# 4_rf_path.net
KiCad netlist of a schematic drawn in Altium Designer
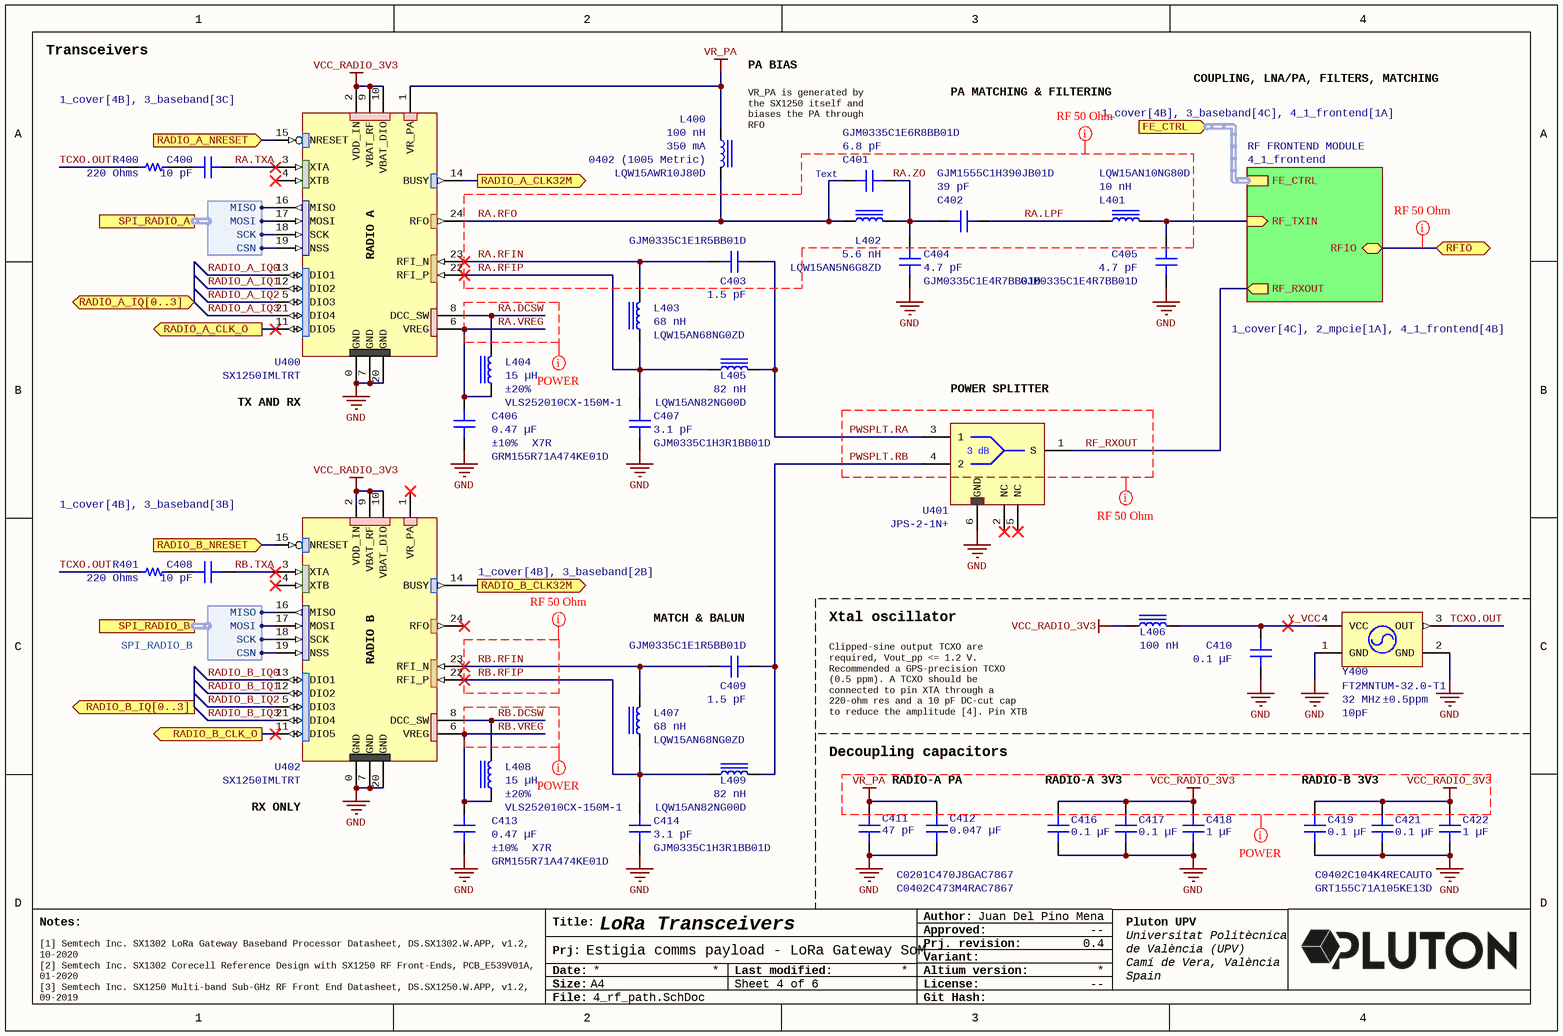
[diagram p0: 4_rf_path.SchDoc]

(export (version "E")
  (design (tool "Eeschema 10.0.6"))
  (components
    (comp (ref "C400")
      (value "10 pF")
      (footprint "CAP 0201_0603")
      (description "CAP CER 10PF 25V C0G/NP0 0201")
      (fields
        (field (name "PART NUMBER") "GJM0335C1E100GB01D")
        (field (name "MANUFACTURER") "Murata Electronics")
      )
      (libsource (lib "Celestial Altium Library - altium_library") (part "Capacitor"))
    )
    (comp (ref "C401")
      (value "6.8 pF")
      (footprint "CAP 0201_0603 RF")
      (description "CAP CER 6.8PF 25V C0G/NP0 0201")
      (fields
        (field (name "PART NUMBER") "GJM0335C1E6R8BB01D")
        (field (name "MANUFACTURER") "Murata Electronics")
        (field (name "TOLERANCE") "±0.1pF")
      )
      (libsource (lib "Celestial Altium Library - altium_library") (part "Capacitor"))
    )
    (comp (ref "C402")
      (value "39 pF")
      (footprint "CAP 0402_1005 RF")
      (description "CAP CER 39PF 50V C0G/NP0 0402")
      (fields
        (field (name "PART NUMBER") "GJM1555C1H390JB01D")
        (field (name "MANUFACTURER") "Murata Electronics")
        (field (name "TOLERANCE") "±5%")
      )
      (libsource (lib "Celestial Altium Library - altium_library") (part "Capacitor"))
    )
    (comp (ref "C403")
      (value "1.5 pF")
      (footprint "CAP 0201_0603 RF")
      (description "CAP CER 1.5PF 25V C0G/NP0 0201")
      (fields
        (field (name "PART NUMBER") "GJM0335C1E1R5BB01D")
        (field (name "CAPACITANCE") "1.5 pF")
        (field (name "MANUFACTURER") "Murata Electronics")
        (field (name "TOLERANCE") "±0.1pF")
      )
      (libsource (lib "Celestial Altium Library - altium_library") (part "Capacitor"))
    )
    (comp (ref "C404")
      (value "4.7 pF")
      (footprint "CAP 0201_0603 RF")
      (description "CAP CER 4.7PF 25V C0G/NP0 0201")
      (fields
        (field (name "PART NUMBER") "GJM0335C1E4R7BB01D")
        (field (name "MANUFACTURER") "Murata Electronics")
        (field (name "TOLERANCE") "±0.1pF")
      )
      (libsource (lib "Celestial Altium Library - altium_library") (part "Capacitor"))
    )
    (comp (ref "C405")
      (value "4.7 pF")
      (footprint "CAP 0201_0603 RF")
      (description "CAP CER 4.7PF 25V C0G/NP0 0201")
      (fields
        (field (name "PART NUMBER") "GJM0335C1E4R7BB01D")
        (field (name "MANUFACTURER") "Murata Electronics")
        (field (name "TOLERANCE") "±0.1pF")
      )
      (libsource (lib "Celestial Altium Library - altium_library") (part "Capacitor"))
    )
    (comp (ref "C406")
      (value "0.47 µF")
      (footprint "CAP 0402_1005")
      (description "CAP CER 0.47UF 10V X7R 0402")
      (fields
        (field (name "PART NUMBER") "GRM155R71A474KE01D")
        (field (name "MANUFACTURER") "Murata Electronics")
        (field (name "TEMPERATURE COEFFICIENT") "X7R")
        (field (name "TOLERANCE") "±10%")
      )
      (libsource (lib "Celestial Altium Library - altium_library") (part "Capacitor"))
    )
    (comp (ref "C407")
      (value "3.1 pF")
      (footprint "CAP 0201_0603 RF")
      (description "CAP CER 3.1PF 50V C0G/NP0 0201")
      (fields
        (field (name "PART NUMBER") "GJM0335C1H3R1BB01D")
        (field (name "CAPACITANCE") "3.1 pF")
        (field (name "MANUFACTURER") "Murata Electronics")
        (field (name "TOLERANCE") "±0.1pF")
      )
      (libsource (lib "Celestial Altium Library - altium_library") (part "Capacitor"))
    )
    (comp (ref "C408")
      (value "10 pF")
      (footprint "CAP 0201_0603")
      (description "CAP CER 10PF 25V C0G/NP0 0201")
      (fields
        (field (name "PART NUMBER") "GJM0335C1E100GB01D")
        (field (name "MANUFACTURER") "Murata Electronics")
      )
      (libsource (lib "Celestial Altium Library - altium_library") (part "Capacitor"))
    )
    (comp (ref "C409")
      (value "1.5 pF")
      (footprint "CAP 0201_0603 RF")
      (description "CAP CER 1.5PF 25V C0G/NP0 0201")
      (fields
        (field (name "PART NUMBER") "GJM0335C1E1R5BB01D")
        (field (name "CAPACITANCE") "1.5 pF")
        (field (name "MANUFACTURER") "Murata Electronics")
        (field (name "TOLERANCE") "±0.1pF")
      )
      (libsource (lib "Celestial Altium Library - altium_library") (part "Capacitor"))
    )
    (comp (ref "C410")
      (value "0.1 µF")
      (footprint "CAP 0402_1005")
      (description "CAP CER 0402 0.1UF 16V X7R 10%")
      (fields (field (name "PART NUMBER") "C0402C104K4RECAUTO") (field (name "MANUFACTURER") "KEMET"))
      (libsource (lib "Celestial Altium Library - altium_library") (part "Capacitor"))
    )
    (comp (ref "C411")
      (value "47 pF")
      (footprint "CAP 0201_0603")
      (description "CAP CER 47PF 10V C0G/NP0 0201")
      (fields
        (field (name "PART NUMBER") "C0201C470J8GAC7867")
        (field (name "MANUFACTURER") "KEMET")
        (field (name "TOLERANCE") "±5%")
      )
      (libsource (lib "Celestial Altium Library - altium_library") (part "Capacitor"))
    )
    (comp (ref "C412")
      (value "0.047 µF")
      (footprint "CAP 0402_1005")
      (description "CAP CER 0.047UF 16V X7R 0402")
      (fields
        (field (name "PART NUMBER") "C0402C473M4RAC7867")
        (field (name "MANUFACTURER") "KEMET")
        (field (name "TOLERANCE") "±20%")
      )
      (libsource (lib "Celestial Altium Library - altium_library") (part "Capacitor"))
    )
    (comp (ref "C413")
      (value "0.47 µF")
      (footprint "CAP 0402_1005")
      (description "CAP CER 0.47UF 10V X7R 0402")
      (fields
        (field (name "PART NUMBER") "GRM155R71A474KE01D")
        (field (name "MANUFACTURER") "Murata Electronics")
        (field (name "TEMPERATURE COEFFICIENT") "X7R")
        (field (name "TOLERANCE") "±10%")
      )
      (libsource (lib "Celestial Altium Library - altium_library") (part "Capacitor"))
    )
    (comp (ref "C414")
      (value "3.1 pF")
      (footprint "CAP 0201_0603 RF")
      (description "CAP CER 3.1PF 50V C0G/NP0 0201")
      (fields
        (field (name "PART NUMBER") "GJM0335C1H3R1BB01D")
        (field (name "CAPACITANCE") "3.1 pF")
        (field (name "MANUFACTURER") "Murata Electronics")
        (field (name "TOLERANCE") "±0.1pF")
      )
      (libsource (lib "Celestial Altium Library - altium_library") (part "Capacitor"))
    )
    (comp (ref "C416")
      (value "0.1 µF")
      (footprint "CAP 0402_1005")
      (description "CAP CER 0402 0.1UF 16V X7R 10%")
      (fields (field (name "PART NUMBER") "C0402C104K4RECAUTO") (field (name "MANUFACTURER") "KEMET"))
      (libsource (lib "Celestial Altium Library - altium_library") (part "Capacitor"))
    )
    (comp (ref "C417")
      (value "0.1 µF")
      (footprint "CAP 0402_1005")
      (description "CAP CER 0402 0.1UF 16V X7R 10%")
      (fields (field (name "PART NUMBER") "C0402C104K4RECAUTO") (field (name "MANUFACTURER") "KEMET"))
      (libsource (lib "Celestial Altium Library - altium_library") (part "Capacitor"))
    )
    (comp (ref "C418")
      (value "1 µF")
      (footprint "CAP 0402_1005")
      (description "CAP CER 1UF 10V X7S 0402")
      (fields
        (field (name "PART NUMBER") "GRT155C71A105KE13D")
        (field (name "MANUFACTURER") "Murata Electronics")
        (field (name "TOLERANCE") "±10%")
      )
      (libsource (lib "Celestial Altium Library - altium_library") (part "Capacitor"))
    )
    (comp (ref "C419")
      (value "0.1 µF")
      (footprint "CAP 0402_1005")
      (description "CAP CER 0402 0.1UF 16V X7R 10%")
      (fields
        (field (name "PART NUMBER") "C0402C104K4RECAUTO")
        (field (name "MANUFACTURER") "KEMET")
        (field (name "TOLERANCE") "±10%")
      )
      (libsource (lib "Celestial Altium Library - altium_library") (part "Capacitor"))
    )
    (comp (ref "C421")
      (value "0.1 µF")
      (footprint "CAP 0402_1005")
      (description "CAP CER 0402 0.1UF 16V X7R 10%")
      (fields (field (name "PART NUMBER") "C0402C104K4RECAUTO") (field (name "MANUFACTURER") "KEMET"))
      (libsource (lib "Celestial Altium Library - altium_library") (part "Capacitor"))
    )
    (comp (ref "C422")
      (value "1 µF")
      (footprint "CAP 0402_1005")
      (description "CAP CER 1UF 10V X7S 0402")
      (fields
        (field (name "PART NUMBER") "GRT155C71A105KE13D")
        (field (name "MANUFACTURER") "Murata Electronics")
      )
      (libsource (lib "Celestial Altium Library - altium_library") (part "Capacitor"))
    )
    (comp (ref "L400")
      (value "100 nH")
      (footprint "IND 0402_1005 RF WW")
      (description "FIXED IND 100NH 350MA 1OHM SMD")
      (fields
        (field (name "PART NUMBER") "LQW15AWR10J80D")
        (field (name "CURRENT RATING (AMPS)") "350 mA")
        (field (name "DEVICE PACKAGE") "0402 (1005 Metric)")
        (field (name "INDUCTANCE") "100 nH")
        (field (name "MANUFACTURER") "Murata Electronics")
        (field (name "TOLERANCE") "±5%")
      )
      (libsource (lib "Celestial Altium Library - altium_library") (part "Inductor"))
    )
    (comp (ref "L401")
      (value "10 nH")
      (footprint "IND 0402_1005 RF WW")
      (description "FIXED IND 10NH 1.4A 0.081OHM SMD")
      (fields
        (field (name "PART NUMBER") "LQW15AN10NG80D")
        (field (name "MANUFACTURER") "Murata Electronics")
        (field (name "TOLERANCE") "±2%")
      )
      (libsource (lib "Celestial Altium Library - altium_library") (part "Inductor"))
    )
    (comp (ref "L402")
      (value "5.6 nH")
      (footprint "IND 0402_1005 RF WW")
      (description "FIXED IND 5.6NH 1.77A 0.04OHM SM")
      (fields
        (field (name "PART NUMBER") "LQW15AN5N6G8ZD")
        (field (name "MANUFACTURER") "Murata Electronics")
        (field (name "TOLERANCE") "±2%")
      )
      (libsource (lib "Celestial Altium Library - altium_library") (part "Inductor"))
    )
    (comp (ref "L403")
      (value "68 nH")
      (footprint "IND 0402_1005 RF WW")
      (description "FIXED IND 68NH 140MA 1.96OHM SMD")
      (fields
        (field (name "PART NUMBER") "LQW15AN68NG0ZD")
        (field (name "INDUCTANCE") "68 nH")
        (field (name "MANUFACTURER") "Murata Electronics")
        (field (name "TOLERANCE") "±2%")
      )
      (libsource (lib "Celestial Altium Library - altium_library") (part "Inductor"))
    )
    (comp (ref "L404")
      (value "15 µH")
      (footprint "TDK VLS252010CX")
      (description "FIXED IND 15UH 560MA 914MOHM SMD")
      (fields
        (field (name "PART NUMBER") "VLS252010CX-150M-1")
        (field (name "INDUCTANCE") "15 µH")
        (field (name "MANUFACTURER") "TDK Corporation")
        (field (name "TOLERANCE") "±20%")
      )
      (libsource (lib "Celestial Altium Library - altium_library") (part "Inductor"))
    )
    (comp (ref "L405")
      (value "82 nH")
      (footprint "IND 0402_1005 RF WW")
      (description "FIXED IND 82NH 130MA 2.24OHM SMD")
      (fields
        (field (name "PART NUMBER") "LQW15AN82NG00D")
        (field (name "INDUCTANCE") "82 nH")
        (field (name "MANUFACTURER") "Murata Electronics")
        (field (name "TOLERANCE") "±2%")
      )
      (libsource (lib "Celestial Altium Library - altium_library") (part "Inductor"))
    )
    (comp (ref "L406")
      (value "100 nH")
      (footprint "IND 0402_1005 RF WW")
      (description "FIXED IND 100NH 350MA 1OHM SMD")
      (fields
        (field (name "PART NUMBER") "LQW15AWR10J80D")
        (field (name "INDUCTANCE") "100 nH")
        (field (name "MANUFACTURER") "Murata Electronics")
      )
      (libsource (lib "Celestial Altium Library - altium_library") (part "Inductor"))
    )
    (comp (ref "L407")
      (value "68 nH")
      (footprint "IND 0402_1005 RF WW")
      (description "FIXED IND 68NH 140MA 1.96OHM SMD")
      (fields
        (field (name "PART NUMBER") "LQW15AN68NG0ZD")
        (field (name "INDUCTANCE") "68 nH")
        (field (name "MANUFACTURER") "Murata Electronics")
        (field (name "TOLERANCE") "±2%")
      )
      (libsource (lib "Celestial Altium Library - altium_library") (part "Inductor"))
    )
    (comp (ref "L408")
      (value "15 µH")
      (footprint "TDK VLS252010CX")
      (description "FIXED IND 15UH 560MA 914MOHM SMD")
      (fields
        (field (name "PART NUMBER") "VLS252010CX-150M-1")
        (field (name "INDUCTANCE") "15 µH")
        (field (name "MANUFACTURER") "TDK Corporation")
        (field (name "TOLERANCE") "±20%")
      )
      (libsource (lib "Celestial Altium Library - altium_library") (part "Inductor"))
    )
    (comp (ref "L409")
      (value "82 nH")
      (footprint "IND 0402_1005 RF WW")
      (description "FIXED IND 82NH 130MA 2.24OHM SMD")
      (fields
        (field (name "PART NUMBER") "LQW15AN82NG00D")
        (field (name "INDUCTANCE") "82 nH")
        (field (name "MANUFACTURER") "Murata Electronics")
        (field (name "TOLERANCE") "±2%")
      )
      (libsource (lib "Celestial Altium Library - altium_library") (part "Inductor"))
    )
    (comp (ref "R400")
      (value "220 Ohms")
      (footprint "RES 0201_0603")
      (description "RES 220 OHM 1% 1/20W 0201")
      (fields (field (name "PART NUMBER") "RC0201FR-07220RL") (field (name "MANUFACTURER") "Yageo"))
      (libsource (lib "Celestial Altium Library - altium_library") (part "Resistor"))
    )
    (comp (ref "R401")
      (value "220 Ohms")
      (footprint "RES 0201_0603")
      (description "RES 220 OHM 1% 1/20W 0201")
      (fields (field (name "PART NUMBER") "RC0201FR-07220RL") (field (name "MANUFACTURER") "Yageo"))
      (libsource (lib "Celestial Altium Library - altium_library") (part "Resistor"))
    )
    (comp (ref "U400")
      (value "SX1250IMLTRT")
      (footprint "ics:QFN-24")
      (description "Sub-GHz RF Front End device. Supports up to +22 dBm output power on-chip")
      (libsource (lib "lora") (part "SX1250IMLTRT"))
    )
    (comp (ref "U401")
      (value "JPS-2-1N+")
      (footprint "SOP6-BH292-JPS-2-1N")
      (description "Power Splitter/Combiner, 2 Way, 0°, 50Ω, 350 to 550 MHz")
      (libsource (lib "rf") (part "JPS-2-1N+"))
    )
    (comp (ref "U402")
      (value "SX1250IMLTRT")
      (footprint "ics:QFN-24")
      (description "Sub-GHz RF Front End device. Supports up to +22 dBm output power on-chip")
      (libsource (lib "lora") (part "SX1250IMLTRT"))
    )
    (comp (ref "Y400")
      (value "FT2MNTUM-32.0-T1")
      (footprint "TCXO-XTAL-FT2MN")
      (fields
        (field (name "PART NUMBER") "FT2MNTUM-32.0-T1")
        (field (name "FREQUENCY") "32 MHz")
        (field (name "TOLERANCE") "±0.5ppm")
        (field (name "LOAD CAPACITANCE") "10pF")
      )
      (libsource (lib "rf") (part "FT2MNTUM-32.0-T1"))
    )
  )
  (nets
    (net (code "5") (name "/PWSPLT.RA") (class "Default")
      (node (ref "C403") (pin "2") (pinfunction "2_2") (pintype "passive"))
      (node (ref "L405") (pin "2") (pinfunction "2_2") (pintype "passive"))
      (node (ref "U401") (pin "3") (pinfunction "1_3") (pintype "passive"))
    )
    (net (code "6") (name "/PWSPLT.RB") (class "Default")
      (node (ref "C409") (pin "2") (pinfunction "2_2") (pintype "passive"))
      (node (ref "L409") (pin "2") (pinfunction "2_2") (pintype "passive"))
      (node (ref "U401") (pin "4") (pinfunction "2_4") (pintype "passive"))
    )
    (net (code "7") (name "/RA.DCSW") (class "Default")
      (node (ref "L404") (pin "2") (pinfunction "2_2") (pintype "passive"))
      (node (ref "U400") (pin "8") (pinfunction "DCC_SW_8") (pintype "power_in"))
    )
    (net (code "8") (name "/RA.LPF") (class "Default")
      (node (ref "C402") (pin "2") (pinfunction "2_2") (pintype "passive"))
      (node (ref "L401") (pin "1") (pinfunction "1_1") (pintype "passive"))
    )
    (net (code "9") (name "/RA.RFIN") (class "Default")
      (node (ref "C403") (pin "1") (pinfunction "1_1") (pintype "passive"))
      (node (ref "L403") (pin "2") (pinfunction "2_2") (pintype "passive"))
      (node (ref "U400") (pin "23") (pinfunction "RFI_N_23") (pintype "input"))
    )
    (net (code "10") (name "/RA.RFIP") (class "Default")
      (node (ref "C407") (pin "2") (pinfunction "2_2") (pintype "passive"))
      (node (ref "L403") (pin "1") (pinfunction "1_1") (pintype "passive"))
      (node (ref "L405") (pin "1") (pinfunction "1_1") (pintype "passive"))
      (node (ref "U400") (pin "22") (pinfunction "RFI_P_22") (pintype "input"))
    )
    (net (code "11") (name "/RA.RFO") (class "Default")
      (node (ref "C401") (pin "1") (pinfunction "1_1") (pintype "passive"))
      (node (ref "L400") (pin "2") (pinfunction "2_2") (pintype "passive"))
      (node (ref "L402") (pin "1") (pinfunction "1_1") (pintype "passive"))
      (node (ref "U400") (pin "24") (pinfunction "RFO_24") (pintype "output"))
    )
    (net (code "12") (name "/RA.TXA") (class "Default")
      (node (ref "C400") (pin "1") (pinfunction "1_1") (pintype "passive"))
      (node (ref "U400") (pin "3") (pinfunction "XTA_3") (pintype "input"))
    )
    (net (code "13") (name "/RA.VREG") (class "Default")
      (node (ref "C406") (pin "2") (pinfunction "2_2") (pintype "passive"))
      (node (ref "L404") (pin "1") (pinfunction "1_1") (pintype "passive"))
      (node (ref "U400") (pin "6") (pinfunction "VREG_6") (pintype "power_in"))
    )
    (net (code "14") (name "/RA.ZO") (class "Default")
      (node (ref "C401") (pin "2") (pinfunction "2_2") (pintype "passive"))
      (node (ref "C402") (pin "1") (pinfunction "1_1") (pintype "passive"))
      (node (ref "C404") (pin "2") (pinfunction "2_2") (pintype "passive"))
      (node (ref "L402") (pin "2") (pinfunction "2_2") (pintype "passive"))
    )
    (net (code "15") (name "/RADIO_A_CLK32M") (class "Default")
      (node (ref "U400") (pin "14") (pinfunction "BUSY_14") (pintype "output"))
    )
    (net (code "16") (name "/RADIO_A_CLK_O") (class "Default")
      (node (ref "U400") (pin "11") (pinfunction "DIO5_11") (pintype "bidirectional+no_connect"))
    )
    (net (code "17") (name "/RADIO_A_IQ0") (class "Default")
      (node (ref "U400") (pin "13") (pinfunction "DIO1_13") (pintype "bidirectional"))
    )
    (net (code "18") (name "/RADIO_A_IQ1") (class "Default")
      (node (ref "U400") (pin "12") (pinfunction "DIO2_12") (pintype "bidirectional"))
    )
    (net (code "19") (name "/RADIO_A_IQ2") (class "Default")
      (node (ref "U400") (pin "5") (pinfunction "DIO3_5") (pintype "bidirectional"))
    )
    (net (code "20") (name "/RADIO_A_IQ3") (class "Default")
      (node (ref "U400") (pin "21") (pinfunction "DIO4_21") (pintype "bidirectional"))
    )
    (net (code "22") (name "/RADIO_A_NRESET") (class "Default")
      (node (ref "U400") (pin "15") (pinfunction "NRESET_15") (pintype "input"))
    )
    (net (code "23") (name "/RADIO_B_CLK32M") (class "Default")
      (node (ref "U402") (pin "14") (pinfunction "BUSY_14") (pintype "output"))
    )
    (net (code "24") (name "/RADIO_B_CLK_O") (class "Default")
      (node (ref "U402") (pin "11") (pinfunction "DIO5_11") (pintype "bidirectional+no_connect"))
    )
    (net (code "25") (name "/RADIO_B_IQ0") (class "Default")
      (node (ref "U402") (pin "13") (pinfunction "DIO1_13") (pintype "bidirectional"))
    )
    (net (code "26") (name "/RADIO_B_IQ1") (class "Default")
      (node (ref "U402") (pin "12") (pinfunction "DIO2_12") (pintype "bidirectional"))
    )
    (net (code "27") (name "/RADIO_B_IQ2") (class "Default")
      (node (ref "U402") (pin "5") (pinfunction "DIO3_5") (pintype "bidirectional"))
    )
    (net (code "28") (name "/RADIO_B_IQ3") (class "Default")
      (node (ref "U402") (pin "21") (pinfunction "DIO4_21") (pintype "bidirectional"))
    )
    (net (code "30") (name "/RADIO_B_NRESET") (class "Default")
      (node (ref "U402") (pin "15") (pinfunction "NRESET_15") (pintype "input"))
    )
    (net (code "31") (name "/RB.DCSW") (class "Default")
      (node (ref "L408") (pin "2") (pinfunction "2_2") (pintype "passive"))
      (node (ref "U402") (pin "8") (pinfunction "DCC_SW_8") (pintype "power_in"))
    )
    (net (code "32") (name "/RB.RFIN") (class "Default")
      (node (ref "C409") (pin "1") (pinfunction "1_1") (pintype "passive"))
      (node (ref "L407") (pin "2") (pinfunction "2_2") (pintype "passive"))
      (node (ref "U402") (pin "23") (pinfunction "RFI_N_23") (pintype "input"))
    )
    (net (code "33") (name "/RB.RFIP") (class "Default")
      (node (ref "C414") (pin "2") (pinfunction "2_2") (pintype "passive"))
      (node (ref "L407") (pin "1") (pinfunction "1_1") (pintype "passive"))
      (node (ref "L409") (pin "1") (pinfunction "1_1") (pintype "passive"))
      (node (ref "U402") (pin "22") (pinfunction "RFI_P_22") (pintype "input"))
    )
    (net (code "34") (name "/RB.TXA") (class "Default")
      (node (ref "C408") (pin "1") (pinfunction "1_1") (pintype "passive"))
      (node (ref "U402") (pin "3") (pinfunction "XTA_3") (pintype "input"))
    )
    (net (code "35") (name "/RB.VREG") (class "Default")
      (node (ref "C413") (pin "2") (pinfunction "2_2") (pintype "passive"))
      (node (ref "L408") (pin "1") (pinfunction "1_1") (pintype "passive"))
      (node (ref "U402") (pin "6") (pinfunction "VREG_6") (pintype "power_in"))
    )
    (net (code "37") (name "/RF_RXOUT") (class "Default")
      (node (ref "U401") (pin "1") (pinfunction "S_1") (pintype "passive"))
    )
    (net (code "38") (name "/RF_TXIN") (class "Default")
      (node (ref "C405") (pin "2") (pinfunction "2_2") (pintype "passive"))
      (node (ref "L401") (pin "2") (pinfunction "2_2") (pintype "passive"))
    )
    (net (code "39") (name "/TCXO.OUT") (class "Default")
      (node (ref "R400") (pin "1") (pinfunction "1_1") (pintype "passive"))
      (node (ref "R401") (pin "1") (pinfunction "1_1") (pintype "passive"))
      (node (ref "Y400") (pin "3") (pinfunction "OUT_3") (pintype "output"))
    )
    (net (code "43") (name "/Y_VCC") (class "Default")
      (node (ref "C410") (pin "2") (pinfunction "2_2") (pintype "passive"))
      (node (ref "L406") (pin "2") (pinfunction "2_2") (pintype "passive"))
      (node (ref "Y400") (pin "4") (pinfunction "VCC_4") (pintype "power_in"))
    )
    (net (code "44") (name "GND") (class "Default")
      (node (ref "C404") (pin "1") (pinfunction "1_1") (pintype "passive"))
      (node (ref "C405") (pin "1") (pinfunction "1_1") (pintype "passive"))
      (node (ref "C406") (pin "1") (pinfunction "1_1") (pintype "passive"))
      (node (ref "C407") (pin "1") (pinfunction "1_1") (pintype "passive"))
      (node (ref "C410") (pin "1") (pinfunction "1_1") (pintype "passive"))
      (node (ref "C411") (pin "1") (pinfunction "1_1") (pintype "passive"))
      (node (ref "C412") (pin "1") (pinfunction "1_1") (pintype "passive"))
      (node (ref "C413") (pin "1") (pinfunction "1_1") (pintype "passive"))
      (node (ref "C414") (pin "1") (pinfunction "1_1") (pintype "passive"))
      (node (ref "C416") (pin "1") (pinfunction "1_1") (pintype "passive"))
      (node (ref "C417") (pin "1") (pinfunction "1_1") (pintype "passive"))
      (node (ref "C418") (pin "1") (pinfunction "1_1") (pintype "passive"))
      (node (ref "C419") (pin "1") (pinfunction "1_1") (pintype "passive"))
      (node (ref "C421") (pin "1") (pinfunction "1_1") (pintype "passive"))
      (node (ref "C422") (pin "1") (pinfunction "1_1") (pintype "passive"))
      (node (ref "U400") (pin "0") (pinfunction "GND_0") (pintype "power_in"))
      (node (ref "U400") (pin "20") (pinfunction "GND_20") (pintype "power_in"))
      (node (ref "U400") (pin "7") (pinfunction "GND_7") (pintype "power_in"))
      (node (ref "U401") (pin "6") (pinfunction "GND_6") (pintype "power_in"))
      (node (ref "U402") (pin "0") (pinfunction "GND_0") (pintype "power_in"))
      (node (ref "U402") (pin "20") (pinfunction "GND_20") (pintype "power_in"))
      (node (ref "U402") (pin "7") (pinfunction "GND_7") (pintype "power_in"))
      (node (ref "Y400") (pin "1") (pinfunction "GND_1") (pintype "power_in"))
      (node (ref "Y400") (pin "2") (pinfunction "GND_2") (pintype "power_in"))
    )
    (net (code "45") (name "Net-(C400-Pad2)") (class "Default")
      (node (ref "C400") (pin "2") (pinfunction "2_2") (pintype "passive"))
      (node (ref "R400") (pin "2") (pinfunction "2_2") (pintype "passive"))
    )
    (net (code "46") (name "Net-(C408-Pad2)") (class "Default")
      (node (ref "C408") (pin "2") (pinfunction "2_2") (pintype "passive"))
      (node (ref "R401") (pin "2") (pinfunction "2_2") (pintype "passive"))
    )
    (net (code "47") (name "VCC_RADIO_3V3") (class "Default")
      (node (ref "C416") (pin "2") (pinfunction "2_2") (pintype "passive"))
      (node (ref "C417") (pin "2") (pinfunction "2_2") (pintype "passive"))
      (node (ref "C418") (pin "2") (pinfunction "2_2") (pintype "passive"))
      (node (ref "C419") (pin "2") (pinfunction "2_2") (pintype "passive"))
      (node (ref "C421") (pin "2") (pinfunction "2_2") (pintype "passive"))
      (node (ref "C422") (pin "2") (pinfunction "2_2") (pintype "passive"))
      (node (ref "L406") (pin "1") (pinfunction "1_1") (pintype "passive"))
      (node (ref "U400") (pin "10") (pinfunction "VBAT_DIO_10") (pintype "power_in"))
      (node (ref "U400") (pin "2") (pinfunction "VDD_IN_2") (pintype "power_in"))
      (node (ref "U400") (pin "9") (pinfunction "VBAT_RF_9") (pintype "power_in"))
      (node (ref "U402") (pin "10") (pinfunction "VBAT_DIO_10") (pintype "power_in"))
      (node (ref "U402") (pin "2") (pinfunction "VDD_IN_2") (pintype "power_in"))
      (node (ref "U402") (pin "9") (pinfunction "VBAT_RF_9") (pintype "power_in"))
    )
    (net (code "48") (name "VR_PA") (class "Default")
      (node (ref "C411") (pin "2") (pinfunction "2_2") (pintype "passive"))
      (node (ref "C412") (pin "2") (pinfunction "2_2") (pintype "passive"))
      (node (ref "L400") (pin "1") (pinfunction "1_1") (pintype "passive"))
      (node (ref "U400") (pin "1") (pinfunction "VR_PA_1") (pintype "power_in"))
    )
    (net (code "49") (name "unconnected-(U400-MISO-Pad16)") (class "Default")
      (node (ref "U400") (pin "16") (pinfunction "MISO_16") (pintype "output"))
    )
    (net (code "50") (name "unconnected-(U400-MOSI-Pad17)") (class "Default")
      (node (ref "U400") (pin "17") (pinfunction "MOSI_17") (pintype "input"))
    )
    (net (code "51") (name "unconnected-(U400-NSS-Pad19)") (class "Default")
      (node (ref "U400") (pin "19") (pinfunction "NSS_19") (pintype "input"))
    )
    (net (code "52") (name "unconnected-(U400-SCK-Pad18)") (class "Default")
      (node (ref "U400") (pin "18") (pinfunction "SCK_18") (pintype "input"))
    )
    (net (code "53") (name "unconnected-(U400-XTB-Pad4)") (class "Default")
      (node (ref "U400") (pin "4") (pinfunction "XTB_4") (pintype "input+no_connect"))
    )
    (net (code "54") (name "unconnected-(U401-NC-Pad2)") (class "Default")
      (node (ref "U401") (pin "2") (pinfunction "NC_2") (pintype "power_in+no_connect"))
    )
    (net (code "55") (name "unconnected-(U401-NC-Pad5)") (class "Default")
      (node (ref "U401") (pin "5") (pinfunction "NC_5") (pintype "power_in+no_connect"))
    )
    (net (code "56") (name "unconnected-(U402-MISO-Pad16)") (class "Default")
      (node (ref "U402") (pin "16") (pinfunction "MISO_16") (pintype "output"))
    )
    (net (code "57") (name "unconnected-(U402-MOSI-Pad17)") (class "Default")
      (node (ref "U402") (pin "17") (pinfunction "MOSI_17") (pintype "input"))
    )
    (net (code "58") (name "unconnected-(U402-NSS-Pad19)") (class "Default")
      (node (ref "U402") (pin "19") (pinfunction "NSS_19") (pintype "input"))
    )
    (net (code "59") (name "unconnected-(U402-RFO-Pad24)") (class "Default")
      (node (ref "U402") (pin "24") (pinfunction "RFO_24") (pintype "output+no_connect"))
    )
    (net (code "60") (name "unconnected-(U402-SCK-Pad18)") (class "Default")
      (node (ref "U402") (pin "18") (pinfunction "SCK_18") (pintype "input"))
    )
    (net (code "61") (name "unconnected-(U402-VR_PA-Pad1)") (class "Default")
      (node (ref "U402") (pin "1") (pinfunction "VR_PA_1") (pintype "power_in+no_connect"))
    )
    (net (code "62") (name "unconnected-(U402-XTB-Pad4)") (class "Default")
      (node (ref "U402") (pin "4") (pinfunction "XTB_4") (pintype "input+no_connect"))
    )
  )
)
